# Controller.net
KiCad netlist of a schematic drawn in Altium Designer
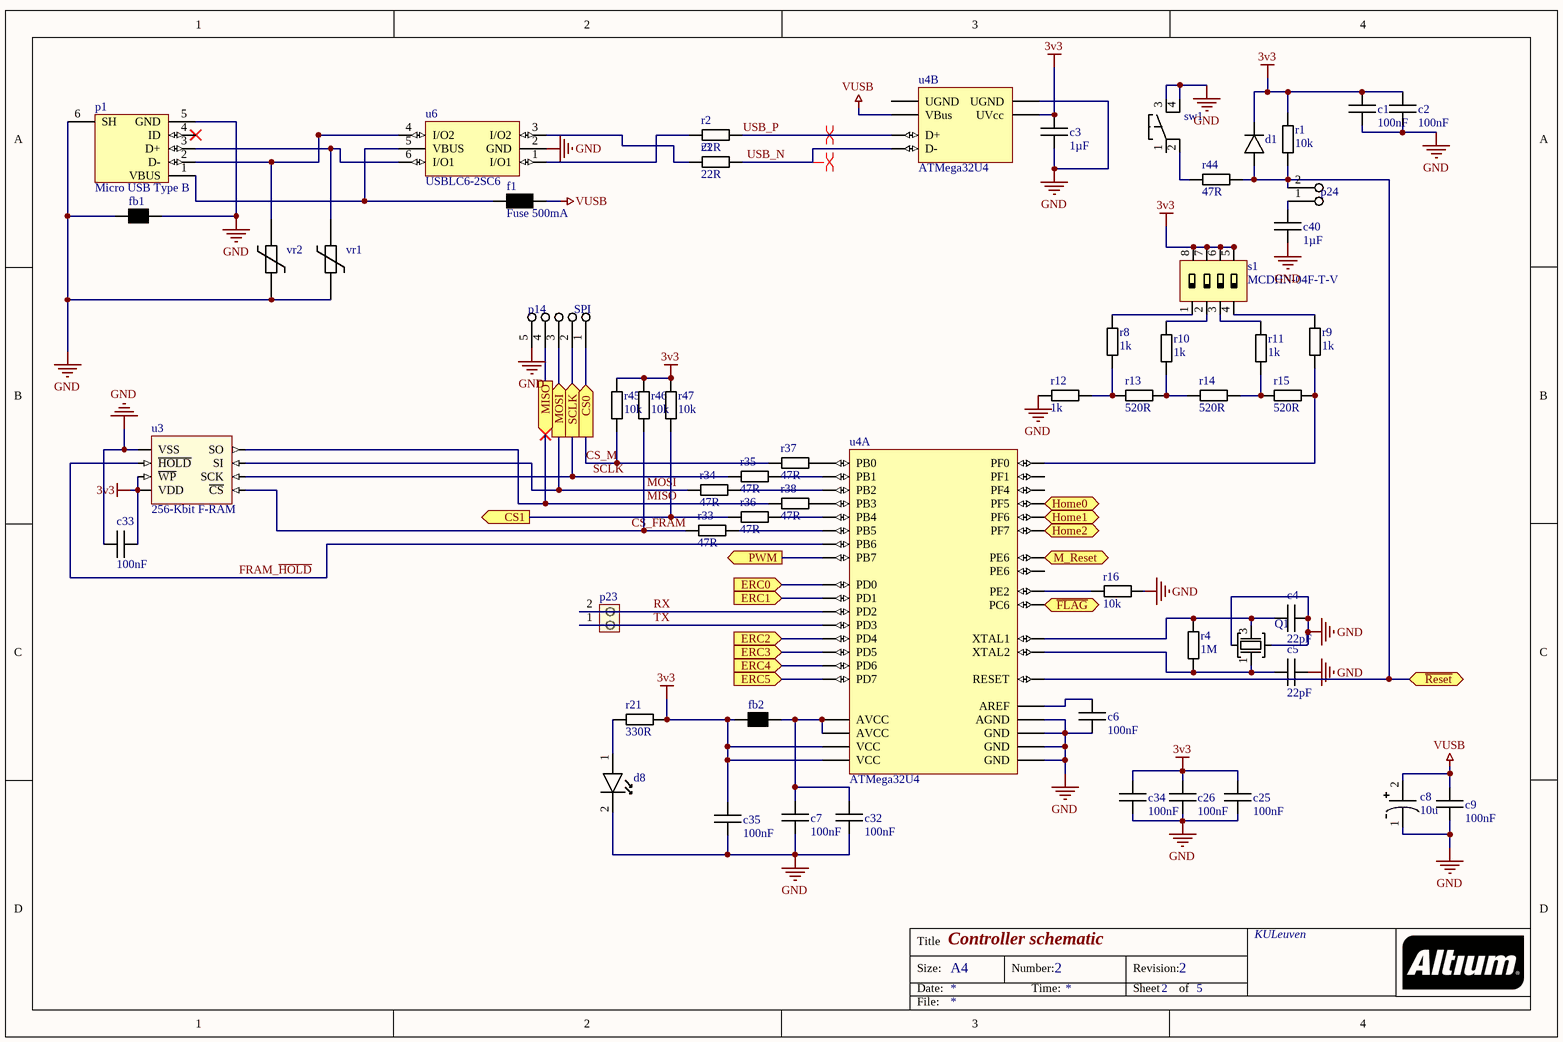
[diagram p0: Controller.SchDoc]

(export (version "E")
  (design (tool "Eeschema 10.0.6"))
  (components
    (comp (ref "c1")
      (value "100nF")
      (footprint "0603")
      (description "...F")
      (libsource (lib "Generic R-C") (part "0603 Capacitor"))
    )
    (comp (ref "c2")
      (value "100nF")
      (footprint "0603")
      (description "...F")
      (libsource (lib "Generic R-C") (part "0603 Capacitor"))
    )
    (comp (ref "c3")
      (value "1µF")
      (footprint "0603")
      (description "...F")
      (libsource (lib "Generic R-C") (part "0603 Capacitor"))
    )
    (comp (ref "c4")
      (value "22pF")
      (footprint "0603")
      (description "...F")
      (libsource (lib "Generic R-C") (part "0603 Capacitor"))
    )
    (comp (ref "c5")
      (value "22pF")
      (footprint "0603")
      (description "...F")
      (libsource (lib "Generic R-C") (part "0603 Capacitor"))
    )
    (comp (ref "c6")
      (value "100nF")
      (footprint "0603")
      (description "...F")
      (libsource (lib "Generic R-C") (part "0603 Capacitor"))
    )
    (comp (ref "c7")
      (value "100nF")
      (footprint "0603")
      (description "...F")
      (libsource (lib "Generic R-C") (part "0603 Capacitor"))
    )
    (comp (ref "c8") (value "10u") (footprint "Elco-C") (libsource (lib "Panasonic") (part "Elco C")))
    (comp (ref "c9")
      (value "100nF")
      (footprint "0603")
      (description "...F")
      (libsource (lib "Generic R-C") (part "0603 Capacitor"))
    )
    (comp (ref "c25")
      (value "100nF")
      (footprint "0603")
      (description "...F")
      (libsource (lib "Generic R-C") (part "0603 Capacitor"))
    )
    (comp (ref "c26")
      (value "100nF")
      (footprint "0603")
      (description "...F")
      (libsource (lib "Generic R-C") (part "0603 Capacitor"))
    )
    (comp (ref "c32")
      (value "100nF")
      (footprint "0603")
      (description "...F")
      (libsource (lib "Generic R-C") (part "0603 Capacitor"))
    )
    (comp (ref "c33")
      (value "100nF")
      (footprint "0603")
      (description "...F")
      (libsource (lib "Generic R-C") (part "0603 Capacitor"))
    )
    (comp (ref "c34")
      (value "100nF")
      (footprint "0603")
      (description "...F")
      (libsource (lib "Generic R-C") (part "0603 Capacitor"))
    )
    (comp (ref "c35")
      (value "100nF")
      (footprint "0603")
      (description "...F")
      (libsource (lib "Generic R-C") (part "0603 Capacitor"))
    )
    (comp (ref "c40")
      (value "1µF")
      (footprint "0603")
      (description "...F")
      (libsource (lib "Generic R-C") (part "0603 Capacitor"))
    )
    (comp (ref "d1")
      (value "CD1206-S01575")
      (footprint "1206 - DIODE")
      (description "Switching Chip Diode")
      (libsource (lib "Bourns") (part "CD1206-S01575"))
    )
    (comp (ref "d8")
      (value "Green SMD LED")
      (footprint "0603 - LED")
      (description "0603 Package")
      (libsource (lib "Kingbright") (part "Green SMD LED"))
    )
    (comp (ref "f1")
      (value "Fuse 500mA")
      (footprint "PTC Fuses")
      (description "Style 1")
      (libsource (lib "Bourns") (part "MF-MSMF Fuse"))
    )
    (comp (ref "fb1")
      (value "0603 Ferrite Bead")
      (footprint "0603")
      (libsource (lib "muRata") (part "0603 Ferrite Bead"))
    )
    (comp (ref "fb2")
      (value "0603 Ferrite Bead")
      (footprint "0603")
      (libsource (lib "muRata") (part "0603 Ferrite Bead"))
    )
    (comp (ref "p1")
      (value "Micro USB Type B")
      (footprint "Micro USB Type B")
      (description "SMD")
      (libsource (lib "Amphenol") (part "Micro USB Type B"))
    )
    (comp (ref "p14")
      (value "SPI")
      (footprint "1x5-HeaderPin")
      (libsource (lib "Multicomp") (part "5 Pin Header"))
    )
    (comp (ref "p23")
      (value "Wire-to-Board 2P")
      (footprint "WtB-F-2p")
      (libsource (lib "Wurth Electronic") (part "Wire-to-Board 2P"))
    )
    (comp (ref "p24")
      (value "2 Pin Header")
      (footprint "1x2-HeaderPin")
      (libsource (lib "Multicomp") (part "2 Pin Header"))
    )
    (comp (ref "Q1")
      (value "Crystal 16MHz, 3.2x2.5mm")
      (footprint "X32")
      (description "X32")
      (libsource (lib "Mercury") (part "Crystal 16MHz, 3.2x2.5mm"))
    )
    (comp (ref "r1")
      (value "10k")
      (footprint "0603")
      (description "...R")
      (libsource (lib "Generic R-C") (part "0603 Resistor"))
    )
    (comp (ref "r2")
      (value "22R")
      (footprint "0603")
      (description "...R")
      (libsource (lib "Generic R-C") (part "0603 Resistor"))
    )
    (comp (ref "r3")
      (value "22R")
      (footprint "0603")
      (description "...R")
      (libsource (lib "Generic R-C") (part "0603 Resistor"))
    )
    (comp (ref "r4")
      (value "1M")
      (footprint "0603")
      (description "...R")
      (libsource (lib "Generic R-C") (part "0603 Resistor"))
    )
    (comp (ref "r8")
      (value "1k")
      (footprint "0603")
      (description "...R")
      (libsource (lib "Generic R-C") (part "0603 Resistor"))
    )
    (comp (ref "r9")
      (value "1k")
      (footprint "0603")
      (description "...R")
      (libsource (lib "Generic R-C") (part "0603 Resistor"))
    )
    (comp (ref "r10")
      (value "1k")
      (footprint "0603")
      (description "...R")
      (libsource (lib "Generic R-C") (part "0603 Resistor"))
    )
    (comp (ref "r11")
      (value "1k")
      (footprint "0603")
      (description "...R")
      (libsource (lib "Generic R-C") (part "0603 Resistor"))
    )
    (comp (ref "r12")
      (value "1k")
      (footprint "0603")
      (description "...R")
      (libsource (lib "Generic R-C") (part "0603 Resistor"))
    )
    (comp (ref "r13")
      (value "520R")
      (footprint "0603")
      (description "...R")
      (libsource (lib "Generic R-C") (part "0603 Resistor"))
    )
    (comp (ref "r14")
      (value "520R")
      (footprint "0603")
      (description "...R")
      (libsource (lib "Generic R-C") (part "0603 Resistor"))
    )
    (comp (ref "r15")
      (value "520R")
      (footprint "0603")
      (description "...R")
      (libsource (lib "Generic R-C") (part "0603 Resistor"))
    )
    (comp (ref "r16")
      (value "10k")
      (footprint "0603")
      (description "...R")
      (libsource (lib "Generic R-C") (part "0603 Resistor"))
    )
    (comp (ref "r21")
      (value "330R")
      (footprint "0603")
      (description "...R")
      (libsource (lib "Generic R-C") (part "0603 Resistor"))
    )
    (comp (ref "r33")
      (value "47R")
      (footprint "0603")
      (description "...R")
      (libsource (lib "Generic R-C") (part "0603 Resistor"))
    )
    (comp (ref "r34")
      (value "47R")
      (footprint "0603")
      (description "...R")
      (libsource (lib "Generic R-C") (part "0603 Resistor"))
    )
    (comp (ref "r35")
      (value "47R")
      (footprint "0603")
      (description "...R")
      (libsource (lib "Generic R-C") (part "0603 Resistor"))
    )
    (comp (ref "r36")
      (value "47R")
      (footprint "0603")
      (description "...R")
      (libsource (lib "Generic R-C") (part "0603 Resistor"))
    )
    (comp (ref "r37")
      (value "47R")
      (footprint "0603")
      (description "...R")
      (libsource (lib "Generic R-C") (part "0603 Resistor"))
    )
    (comp (ref "r38")
      (value "47R")
      (footprint "0603")
      (description "...R")
      (libsource (lib "Generic R-C") (part "0603 Resistor"))
    )
    (comp (ref "r44")
      (value "47R")
      (footprint "0603")
      (description "...R")
      (libsource (lib "Generic R-C") (part "0603 Resistor"))
    )
    (comp (ref "r45")
      (value "10k")
      (footprint "0603")
      (description "...R")
      (libsource (lib "Generic R-C") (part "0603 Resistor"))
    )
    (comp (ref "r46")
      (value "10k")
      (footprint "0603")
      (description "...R")
      (libsource (lib "Generic R-C") (part "0603 Resistor"))
    )
    (comp (ref "r47")
      (value "10k")
      (footprint "0603")
      (description "...R")
      (libsource (lib "Generic R-C") (part "0603 Resistor"))
    )
    (comp (ref "s1")
      (value "MCDHN-04F-T-V")
      (footprint "Dipswitch-4")
      (description "Dipswitch 4 way")
      (libsource (lib "Multicomp") (part "MCDHN-04F-T-V"))
    )
    (comp (ref "sw1")
      (value "MCDTSJW-6")
      (footprint "MCDTSJW6")
      (description "Push button")
      (libsource (lib "Multicomp") (part "MCDTSJW-6"))
    )
    (comp (ref "u3")
      (value "256-Kbit F-RAM")
      (footprint "SOIC8N")
      (description "256-Kbit (32Kx8) Serial SPI F-RAM")
      (libsource (lib "Cypress") (part "FM25W256"))
    )
    (comp (ref "u4")
      (value "ATMega32U4")
      (footprint "TQFP-44")
      (libsource (lib "Microchip-Atmel") (part "ATMega32U4"))
    )
    (comp (ref "u6")
      (value "USBLC6-2SC6")
      (footprint "SOT23-6")
      (description "SOT23-6 ESD")
      (libsource (lib "STMicroelectronics") (part "USBLC6-2SC6"))
    )
    (comp (ref "vr1")
      (value "CG0603MLC-05E")
      (footprint "0603")
      (description "5V, 8V Varistor - 0603")
      (libsource (lib "Bourns") (part "CG0603MLC-05E"))
    )
    (comp (ref "vr2")
      (value "CG0603MLC-05E")
      (footprint "0603")
      (description "5V, 8V Varistor - 0603")
      (libsource (lib "Bourns") (part "CG0603MLC-05E"))
    )
  )
  (nets
    (net (code "1") (name "/CS1") (class "Default")
      (node (ref "r36") (pin "1") (pintype "passive"))
      (node (ref "r47") (pin "1") (pintype "passive"))
    )
    (net (code "2") (name "/CS_FRAM") (class "Default")
      (node (ref "r33") (pin "1") (pintype "passive"))
      (node (ref "r46") (pin "1") (pintype "passive"))
      (node (ref "u3") (pin "1") (pinfunction "~{CS}_1") (pintype "input"))
    )
    (net (code "3") (name "/CS_M") (class "Default")
      (node (ref "p14") (pin "1") (pinfunction "1_1") (pintype "passive"))
      (node (ref "r37") (pin "1") (pintype "passive"))
      (node (ref "r45") (pin "1") (pintype "passive"))
    )
    (net (code "4") (name "/ERC0") (class "Default")
      (node (ref "u4") (pin "18") (pinfunction "PD0_18") (pintype "bidirectional"))
    )
    (net (code "5") (name "/ERC1") (class "Default")
      (node (ref "u4") (pin "19") (pinfunction "PD1_19") (pintype "bidirectional"))
    )
    (net (code "6") (name "/ERC2") (class "Default")
      (node (ref "u4") (pin "25") (pinfunction "PD4_25") (pintype "bidirectional"))
    )
    (net (code "7") (name "/ERC3") (class "Default")
      (node (ref "u4") (pin "22") (pinfunction "PD5_22") (pintype "bidirectional"))
    )
    (net (code "8") (name "/ERC4") (class "Default")
      (node (ref "u4") (pin "26") (pinfunction "PD6_26") (pintype "bidirectional"))
    )
    (net (code "9") (name "/ERC5") (class "Default")
      (node (ref "u4") (pin "27") (pinfunction "PD7_27") (pintype "bidirectional"))
    )
    (net (code "10") (name "/FRAM_~{HOLD}") (class "Default")
      (node (ref "u3") (pin "7") (pinfunction "~{HOLD}_7") (pintype "input"))
      (node (ref "u4") (pin "30") (pinfunction "PB6_30") (pintype "bidirectional"))
    )
    (net (code "14") (name "/Home0") (class "Default")
      (node (ref "u4") (pin "38") (pinfunction "PF5_38") (pintype "bidirectional"))
    )
    (net (code "15") (name "/Home1") (class "Default")
      (node (ref "u4") (pin "37") (pinfunction "PF6_37") (pintype "bidirectional"))
    )
    (net (code "17") (name "/Home2") (class "Default")
      (node (ref "u4") (pin "36") (pinfunction "PF7_36") (pintype "bidirectional"))
    )
    (net (code "18") (name "/MISO") (class "Default")
      (node (ref "p14") (pin "4") (pinfunction "4_4") (pintype "passive"))
      (node (ref "r38") (pin "1") (pintype "passive"))
      (node (ref "u3") (pin "2") (pinfunction "SO_2") (pintype "output"))
    )
    (net (code "19") (name "/MOSI") (class "Default")
      (node (ref "p14") (pin "3") (pinfunction "3_3") (pintype "passive"))
      (node (ref "r34") (pin "1") (pintype "passive"))
      (node (ref "u3") (pin "5") (pinfunction "SI_5") (pintype "input"))
    )
    (net (code "20") (name "/M_Reset") (class "Default")
      (node (ref "u4") (pin "1") (pinfunction "PE6_1") (pintype "bidirectional"))
    )
    (net (code "21") (name "/PWM") (class "Default")
      (node (ref "u4") (pin "12") (pinfunction "PB7_12") (pintype "bidirectional"))
    )
    (net (code "22") (name "/RX") (class "Default")
      (node (ref "p23") (pin "2") (pinfunction "2_2") (pintype "passive"))
      (node (ref "u4") (pin "20") (pinfunction "PD2_20") (pintype "bidirectional"))
    )
    (net (code "24") (name "/SCLK") (class "Default")
      (node (ref "p14") (pin "2") (pinfunction "2_2") (pintype "passive"))
      (node (ref "r35") (pin "1") (pintype "passive"))
      (node (ref "u3") (pin "6") (pinfunction "SCK_6") (pintype "input"))
    )
    (net (code "25") (name "/TX") (class "Default")
      (node (ref "p23") (pin "1") (pinfunction "1_1") (pintype "passive"))
      (node (ref "u4") (pin "21") (pinfunction "PD3_21") (pintype "bidirectional"))
    )
    (net (code "26") (name "/USB_N") (class "Default")
      (node (ref "r3") (pin "2") (pintype "passive"))
      (node (ref "u4") (pin "3") (pinfunction "D-_3") (pintype "bidirectional"))
    )
    (net (code "27") (name "/USB_P") (class "Default")
      (node (ref "r2") (pin "2") (pintype "passive"))
      (node (ref "u4") (pin "4") (pinfunction "D+_4") (pintype "bidirectional"))
    )
    (net (code "28") (name "/~{FLAG}") (class "Default")
      (node (ref "u4") (pin "31") (pinfunction "PC6_31") (pintype "bidirectional"))
    )
    (net (code "29") (name "/~{Reset}") (class "Default")
      (node (ref "d1") (pin "2") (pinfunction "Anode_2") (pintype "passive"))
      (node (ref "p24") (pin "2") (pinfunction "2_2") (pintype "passive"))
      (node (ref "r1") (pin "1") (pintype "passive"))
      (node (ref "r44") (pin "2") (pintype "passive"))
      (node (ref "u4") (pin "13") (pinfunction "RESET_13") (pintype "bidirectional"))
    )
    (net (code "30") (name "3v3") (class "Default")
      (node (ref "c1") (pin "1") (pinfunction "1_1") (pintype "passive"))
      (node (ref "c2") (pin "1") (pinfunction "1_1") (pintype "passive"))
      (node (ref "c25") (pin "1") (pinfunction "1_1") (pintype "passive"))
      (node (ref "c26") (pin "1") (pinfunction "1_1") (pintype "passive"))
      (node (ref "c3") (pin "1") (pinfunction "1_1") (pintype "passive"))
      (node (ref "c33") (pin "2") (pinfunction "2_2") (pintype "passive"))
      (node (ref "c34") (pin "1") (pinfunction "1_1") (pintype "passive"))
      (node (ref "c35") (pin "1") (pinfunction "1_1") (pintype "passive"))
      (node (ref "d1") (pin "1") (pinfunction "Kathode_1") (pintype "passive"))
      (node (ref "fb2") (pin "1") (pintype "passive"))
      (node (ref "r1") (pin "2") (pintype "passive"))
      (node (ref "r21") (pin "2") (pintype "passive"))
      (node (ref "r45") (pin "2") (pintype "passive"))
      (node (ref "r46") (pin "2") (pintype "passive"))
      (node (ref "r47") (pin "2") (pintype "passive"))
      (node (ref "s1") (pin "5") (pinfunction "5_5") (pintype "passive"))
      (node (ref "s1") (pin "6") (pinfunction "6_6") (pintype "passive"))
      (node (ref "s1") (pin "7") (pinfunction "7_7") (pintype "passive"))
      (node (ref "s1") (pin "8") (pinfunction "8_8") (pintype "passive"))
      (node (ref "u3") (pin "3") (pinfunction "~{WP}_3") (pintype "input"))
      (node (ref "u3") (pin "8") (pinfunction "VDD_8") (pintype "power_in"))
      (node (ref "u4") (pin "14") (pinfunction "VCC_14") (pintype "power_in"))
      (node (ref "u4") (pin "2") (pinfunction "UVcc_2") (pintype "power_in"))
      (node (ref "u4") (pin "34") (pinfunction "VCC_34") (pintype "power_in"))
    )
    (net (code "31") (name "GND") (class "Default")
      (node (ref "Q1") (pin "2") (pinfunction "2_2") (pintype "passive"))
      (node (ref "Q1") (pin "4") (pinfunction "4_4") (pintype "passive"))
      (node (ref "c1") (pin "2") (pinfunction "2_2") (pintype "passive"))
      (node (ref "c2") (pin "2") (pinfunction "2_2") (pintype "passive"))
      (node (ref "c25") (pin "2") (pinfunction "2_2") (pintype "passive"))
      (node (ref "c26") (pin "2") (pinfunction "2_2") (pintype "passive"))
      (node (ref "c3") (pin "2") (pinfunction "2_2") (pintype "passive"))
      (node (ref "c32") (pin "2") (pinfunction "2_2") (pintype "passive"))
      (node (ref "c33") (pin "1") (pinfunction "1_1") (pintype "passive"))
      (node (ref "c34") (pin "2") (pinfunction "2_2") (pintype "passive"))
      (node (ref "c35") (pin "2") (pinfunction "2_2") (pintype "passive"))
      (node (ref "c4") (pin "2") (pinfunction "2_2") (pintype "passive"))
      (node (ref "c40") (pin "1") (pinfunction "1_1") (pintype "passive"))
      (node (ref "c5") (pin "2") (pinfunction "2_2") (pintype "passive"))
      (node (ref "c6") (pin "1") (pinfunction "1_1") (pintype "passive"))
      (node (ref "c7") (pin "2") (pinfunction "2_2") (pintype "passive"))
      (node (ref "c8") (pin "1") (pintype "passive"))
      (node (ref "c9") (pin "2") (pinfunction "2_2") (pintype "passive"))
      (node (ref "d8") (pin "2") (pinfunction "Kathode_2") (pintype "passive"))
      (node (ref "fb1") (pin "1") (pintype "passive"))
      (node (ref "fb1") (pin "2") (pintype "passive"))
      (node (ref "p1") (pin "5") (pinfunction "GND_5") (pintype "power_in"))
      (node (ref "p1") (pin "6") (pinfunction "SH_6") (pintype "power_in"))
      (node (ref "p14") (pin "5") (pinfunction "5_5") (pintype "passive"))
      (node (ref "r12") (pin "2") (pintype "passive"))
      (node (ref "r16") (pin "1") (pintype "passive"))
      (node (ref "sw1") (pin "3") (pinfunction "3_3") (pintype "passive"))
      (node (ref "sw1") (pin "4") (pinfunction "4_4") (pintype "passive"))
      (node (ref "u3") (pin "4") (pinfunction "VSS_4") (pintype "power_in"))
      (node (ref "u4") (pin "15") (pinfunction "GND_15") (pintype "power_in"))
      (node (ref "u4") (pin "23") (pinfunction "GND_23") (pintype "power_in"))
      (node (ref "u4") (pin "35") (pinfunction "GND_35") (pintype "power_in"))
      (node (ref "u4") (pin "43") (pinfunction "AGND_43") (pintype "power_in"))
      (node (ref "u4") (pin "5") (pinfunction "UGND_5") (pintype "power_in"))
      (node (ref "u6") (pin "2") (pinfunction "GND_2") (pintype "power_in"))
      (node (ref "vr1") (pin "1") (pintype "passive"))
      (node (ref "vr2") (pin "1") (pintype "passive"))
    )
    (net (code "32") (name "Net-(c32-Pad1)") (class "Default")
      (node (ref "c32") (pin "1") (pinfunction "1_1") (pintype "passive"))
      (node (ref "c7") (pin "1") (pinfunction "1_1") (pintype "passive"))
      (node (ref "fb2") (pin "2") (pintype "passive"))
      (node (ref "u4") (pin "24") (pinfunction "AVCC_24") (pintype "power_in"))
      (node (ref "u4") (pin "44") (pinfunction "AVCC_44") (pintype "power_in"))
    )
    (net (code "33") (name "Net-(c40-Pad2)") (class "Default")
      (node (ref "c40") (pin "2") (pinfunction "2_2") (pintype "passive"))
      (node (ref "p24") (pin "1") (pinfunction "1_1") (pintype "passive"))
    )
    (net (code "34") (name "Net-(d8-Anode)") (class "Default")
      (node (ref "d8") (pin "1") (pinfunction "Anode_1") (pintype "passive"))
      (node (ref "r21") (pin "1") (pintype "passive"))
    )
    (net (code "35") (name "Net-(p1-D+)") (class "Default")
      (node (ref "p1") (pin "3") (pinfunction "D+_3") (pintype "bidirectional"))
      (node (ref "u6") (pin "6") (pinfunction "I/O1_6") (pintype "bidirectional"))
      (node (ref "vr1") (pin "2") (pintype "passive"))
    )
    (net (code "36") (name "Net-(p1-D-)") (class "Default")
      (node (ref "p1") (pin "2") (pinfunction "D-_2") (pintype "bidirectional"))
      (node (ref "u6") (pin "4") (pinfunction "I/O2_4") (pintype "bidirectional"))
      (node (ref "vr2") (pin "2") (pintype "passive"))
    )
    (net (code "37") (name "Net-(p1-VBUS)") (class "Default")
      (node (ref "f1") (pin "1") (pintype "passive"))
      (node (ref "p1") (pin "1") (pinfunction "VBUS_1") (pintype "power_in"))
      (node (ref "u6") (pin "5") (pinfunction "VBUS_5") (pintype "power_in"))
    )
    (net (code "38") (name "Net-(r2-Pad1)") (class "Default")
      (node (ref "r2") (pin "1") (pintype "passive"))
      (node (ref "u6") (pin "1") (pinfunction "I/O1_1") (pintype "bidirectional"))
    )
    (net (code "39") (name "Net-(r3-Pad1)") (class "Default")
      (node (ref "r3") (pin "1") (pintype "passive"))
      (node (ref "u6") (pin "3") (pinfunction "I/O2_3") (pintype "bidirectional"))
    )
    (net (code "40") (name "Net-(r8-Pad2)") (class "Default")
      (node (ref "r8") (pin "2") (pintype "passive"))
      (node (ref "s1") (pin "1") (pinfunction "1_1") (pintype "passive"))
    )
    (net (code "41") (name "Net-(r9-Pad2)") (class "Default")
      (node (ref "r9") (pin "2") (pintype "passive"))
      (node (ref "s1") (pin "4") (pinfunction "4_4") (pintype "passive"))
    )
    (net (code "42") (name "Net-(r10-Pad1)") (class "Default")
      (node (ref "r10") (pin "1") (pintype "passive"))
      (node (ref "r13") (pin "1") (pintype "passive"))
      (node (ref "r14") (pin "2") (pintype "passive"))
    )
    (net (code "43") (name "Net-(r10-Pad2)") (class "Default")
      (node (ref "r10") (pin "2") (pintype "passive"))
      (node (ref "s1") (pin "2") (pinfunction "2_2") (pintype "passive"))
    )
    (net (code "44") (name "Net-(r11-Pad1)") (class "Default")
      (node (ref "r11") (pin "1") (pintype "passive"))
      (node (ref "r14") (pin "1") (pintype "passive"))
      (node (ref "r15") (pin "2") (pintype "passive"))
    )
    (net (code "45") (name "Net-(r11-Pad2)") (class "Default")
      (node (ref "r11") (pin "2") (pintype "passive"))
      (node (ref "s1") (pin "3") (pinfunction "3_3") (pintype "passive"))
    )
    (net (code "46") (name "Net-(r12-Pad1)") (class "Default")
      (node (ref "r12") (pin "1") (pintype "passive"))
      (node (ref "r13") (pin "2") (pintype "passive"))
      (node (ref "r8") (pin "1") (pintype "passive"))
    )
    (net (code "47") (name "Net-(r44-Pad1)") (class "Default")
      (node (ref "r44") (pin "1") (pintype "passive"))
      (node (ref "sw1") (pin "2") (pinfunction "2_2") (pintype "passive"))
    )
    (net (code "48") (name "Net-(u4A-AREF)") (class "Default")
      (node (ref "c6") (pin "2") (pinfunction "2_2") (pintype "passive"))
      (node (ref "u4") (pin "42") (pinfunction "AREF_42") (pintype "power_in"))
    )
    (net (code "49") (name "Net-(u4A-PB0)") (class "Default")
      (node (ref "r37") (pin "2") (pintype "passive"))
      (node (ref "u4") (pin "8") (pinfunction "PB0_8") (pintype "bidirectional"))
    )
    (net (code "50") (name "Net-(u4A-PB1)") (class "Default")
      (node (ref "r35") (pin "2") (pintype "passive"))
      (node (ref "u4") (pin "9") (pinfunction "PB1_9") (pintype "bidirectional"))
    )
    (net (code "51") (name "Net-(u4A-PB2)") (class "Default")
      (node (ref "r34") (pin "2") (pintype "passive"))
      (node (ref "u4") (pin "10") (pinfunction "PB2_10") (pintype "bidirectional"))
    )
    (net (code "52") (name "Net-(u4A-PB3)") (class "Default")
      (node (ref "r38") (pin "2") (pintype "passive"))
      (node (ref "u4") (pin "11") (pinfunction "PB3_11") (pintype "bidirectional"))
    )
    (net (code "53") (name "Net-(u4A-PB4)") (class "Default")
      (node (ref "r36") (pin "2") (pintype "passive"))
      (node (ref "u4") (pin "28") (pinfunction "PB4_28") (pintype "bidirectional"))
    )
    (net (code "54") (name "Net-(u4A-PB5)") (class "Default")
      (node (ref "r33") (pin "2") (pintype "passive"))
      (node (ref "u4") (pin "29") (pinfunction "PB5_29") (pintype "bidirectional"))
    )
    (net (code "55") (name "Net-(u4A-PE2)") (class "Default")
      (node (ref "r16") (pin "2") (pintype "passive"))
      (node (ref "u4") (pin "33") (pinfunction "PE2_33") (pintype "bidirectional"))
    )
    (net (code "56") (name "Net-(u4A-PF0)") (class "Default")
      (node (ref "r15") (pin "1") (pintype "passive"))
      (node (ref "r9") (pin "1") (pintype "passive"))
      (node (ref "u4") (pin "41") (pinfunction "PF0_41") (pintype "bidirectional"))
    )
    (net (code "57") (name "Net-(u4A-XTAL1)") (class "Default")
      (node (ref "Q1") (pin "3") (pinfunction "3_3") (pintype "passive"))
      (node (ref "c4") (pin "1") (pinfunction "1_1") (pintype "passive"))
      (node (ref "r4") (pin "1") (pintype "passive"))
      (node (ref "u4") (pin "17") (pinfunction "XTAL1_17") (pintype "bidirectional"))
    )
    (net (code "58") (name "Net-(u4A-XTAL2)") (class "Default")
      (node (ref "Q1") (pin "1") (pinfunction "1_1") (pintype "passive"))
      (node (ref "c5") (pin "1") (pinfunction "1_1") (pintype "passive"))
      (node (ref "r4") (pin "2") (pintype "passive"))
      (node (ref "u4") (pin "16") (pinfunction "XTAL2_16") (pintype "bidirectional"))
    )
    (net (code "59") (name "VUSB") (class "Default")
      (node (ref "c8") (pin "2") (pintype "passive"))
      (node (ref "c9") (pin "1") (pinfunction "1_1") (pintype "passive"))
      (node (ref "f1") (pin "2") (pintype "passive"))
      (node (ref "u4") (pin "7") (pinfunction "VBus_7") (pintype "power_in"))
    )
    (net (code "60") (name "unconnected-(p1-ID-Pad4)") (class "Default")
      (node (ref "p1") (pin "4") (pinfunction "ID_4") (pintype "bidirectional+no_connect"))
    )
    (net (code "61") (name "unconnected-(sw1-Pad1)") (class "Default")
      (node (ref "sw1") (pin "1") (pinfunction "1_1") (pintype "passive"))
    )
    (net (code "62") (name "unconnected-(u4A-PE6-Pad1)") (class "Default")
      (node (ref "u4") (pin "1") (pinfunction "PE6_1") (pintype "bidirectional"))
    )
    (net (code "63") (name "unconnected-(u4A-PF1-Pad40)") (class "Default")
      (node (ref "u4") (pin "40") (pinfunction "PF1_40") (pintype "bidirectional"))
    )
    (net (code "64") (name "unconnected-(u4A-PF4-Pad39)") (class "Default")
      (node (ref "u4") (pin "39") (pinfunction "PF4_39") (pintype "bidirectional"))
    )
    (net (code "65") (name "unconnected-(u4B-UGND-Pad5)") (class "Default")
      (node (ref "u4") (pin "5") (pinfunction "UGND_5") (pintype "power_in"))
    )
  )
)
